# highSideBreakout.net
KiCad netlist of a schematic drawn in EAGLE
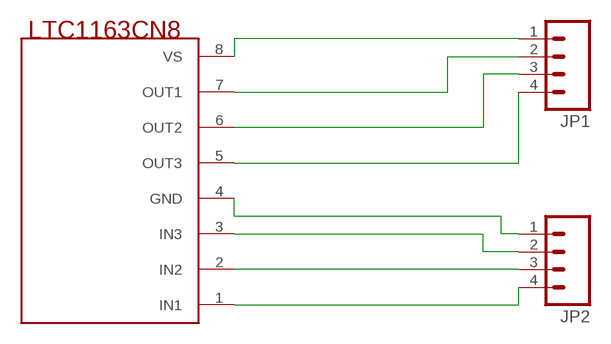
[diagram p0: schematic, sheet 1]

(export (version "E")
  (design (tool "Eeschema 10.0.6"))
  (components
    (comp (ref "JP1")
      (value "M04PTH")
      (footprint "eagle-import:1X04")
      (libsource (lib "eagle-import") (part "M04PTH"))
    )
    (comp (ref "JP2")
      (value "M04PTH")
      (footprint "eagle-import:1X04")
      (libsource (lib "eagle-import") (part "M04PTH"))
    )
    (comp (ref "U$1")
      (value "LTC1163CN8")
      (footprint "eagle-import:SO08")
      (libsource (lib "eagle-import") (part "LTC1163CN8"))
    )
  )
  (nets
    (net (code "1") (name "Net-(U$1-GND)") (class "Default")
      (node (ref "JP2") (pin "1") (pinfunction "1_1") (pintype "passive"))
      (node (ref "U$1") (pin "4") (pinfunction "GND_4") (pintype "bidirectional"))
    )
    (net (code "2") (name "Net-(U$1-IN1)") (class "Default")
      (node (ref "JP2") (pin "4") (pinfunction "4_4") (pintype "passive"))
      (node (ref "U$1") (pin "1") (pinfunction "IN1_1") (pintype "bidirectional"))
    )
    (net (code "3") (name "Net-(U$1-IN2)") (class "Default")
      (node (ref "JP2") (pin "3") (pinfunction "3_3") (pintype "passive"))
      (node (ref "U$1") (pin "2") (pinfunction "IN2_2") (pintype "bidirectional"))
    )
    (net (code "4") (name "Net-(U$1-IN3)") (class "Default")
      (node (ref "JP2") (pin "2") (pinfunction "2_2") (pintype "passive"))
      (node (ref "U$1") (pin "3") (pinfunction "IN3_3") (pintype "bidirectional"))
    )
    (net (code "5") (name "Net-(U$1-OUT1)") (class "Default")
      (node (ref "JP1") (pin "2") (pinfunction "2_2") (pintype "passive"))
      (node (ref "U$1") (pin "7") (pinfunction "OUT1_7") (pintype "bidirectional"))
    )
    (net (code "6") (name "Net-(U$1-OUT2)") (class "Default")
      (node (ref "JP1") (pin "3") (pinfunction "3_3") (pintype "passive"))
      (node (ref "U$1") (pin "6") (pinfunction "OUT2_6") (pintype "bidirectional"))
    )
    (net (code "7") (name "Net-(U$1-OUT3)") (class "Default")
      (node (ref "JP1") (pin "4") (pinfunction "4_4") (pintype "passive"))
      (node (ref "U$1") (pin "5") (pinfunction "OUT3_5") (pintype "bidirectional"))
    )
    (net (code "8") (name "Net-(U$1-VS)") (class "Default")
      (node (ref "JP1") (pin "1") (pinfunction "1_1") (pintype "passive"))
      (node (ref "U$1") (pin "8") (pinfunction "VS_8") (pintype "bidirectional"))
    )
  )
)
